# SCH_TempBoard-vB_2024-06-08.net
KiCad netlist of a schematic drawn in EasyEDA
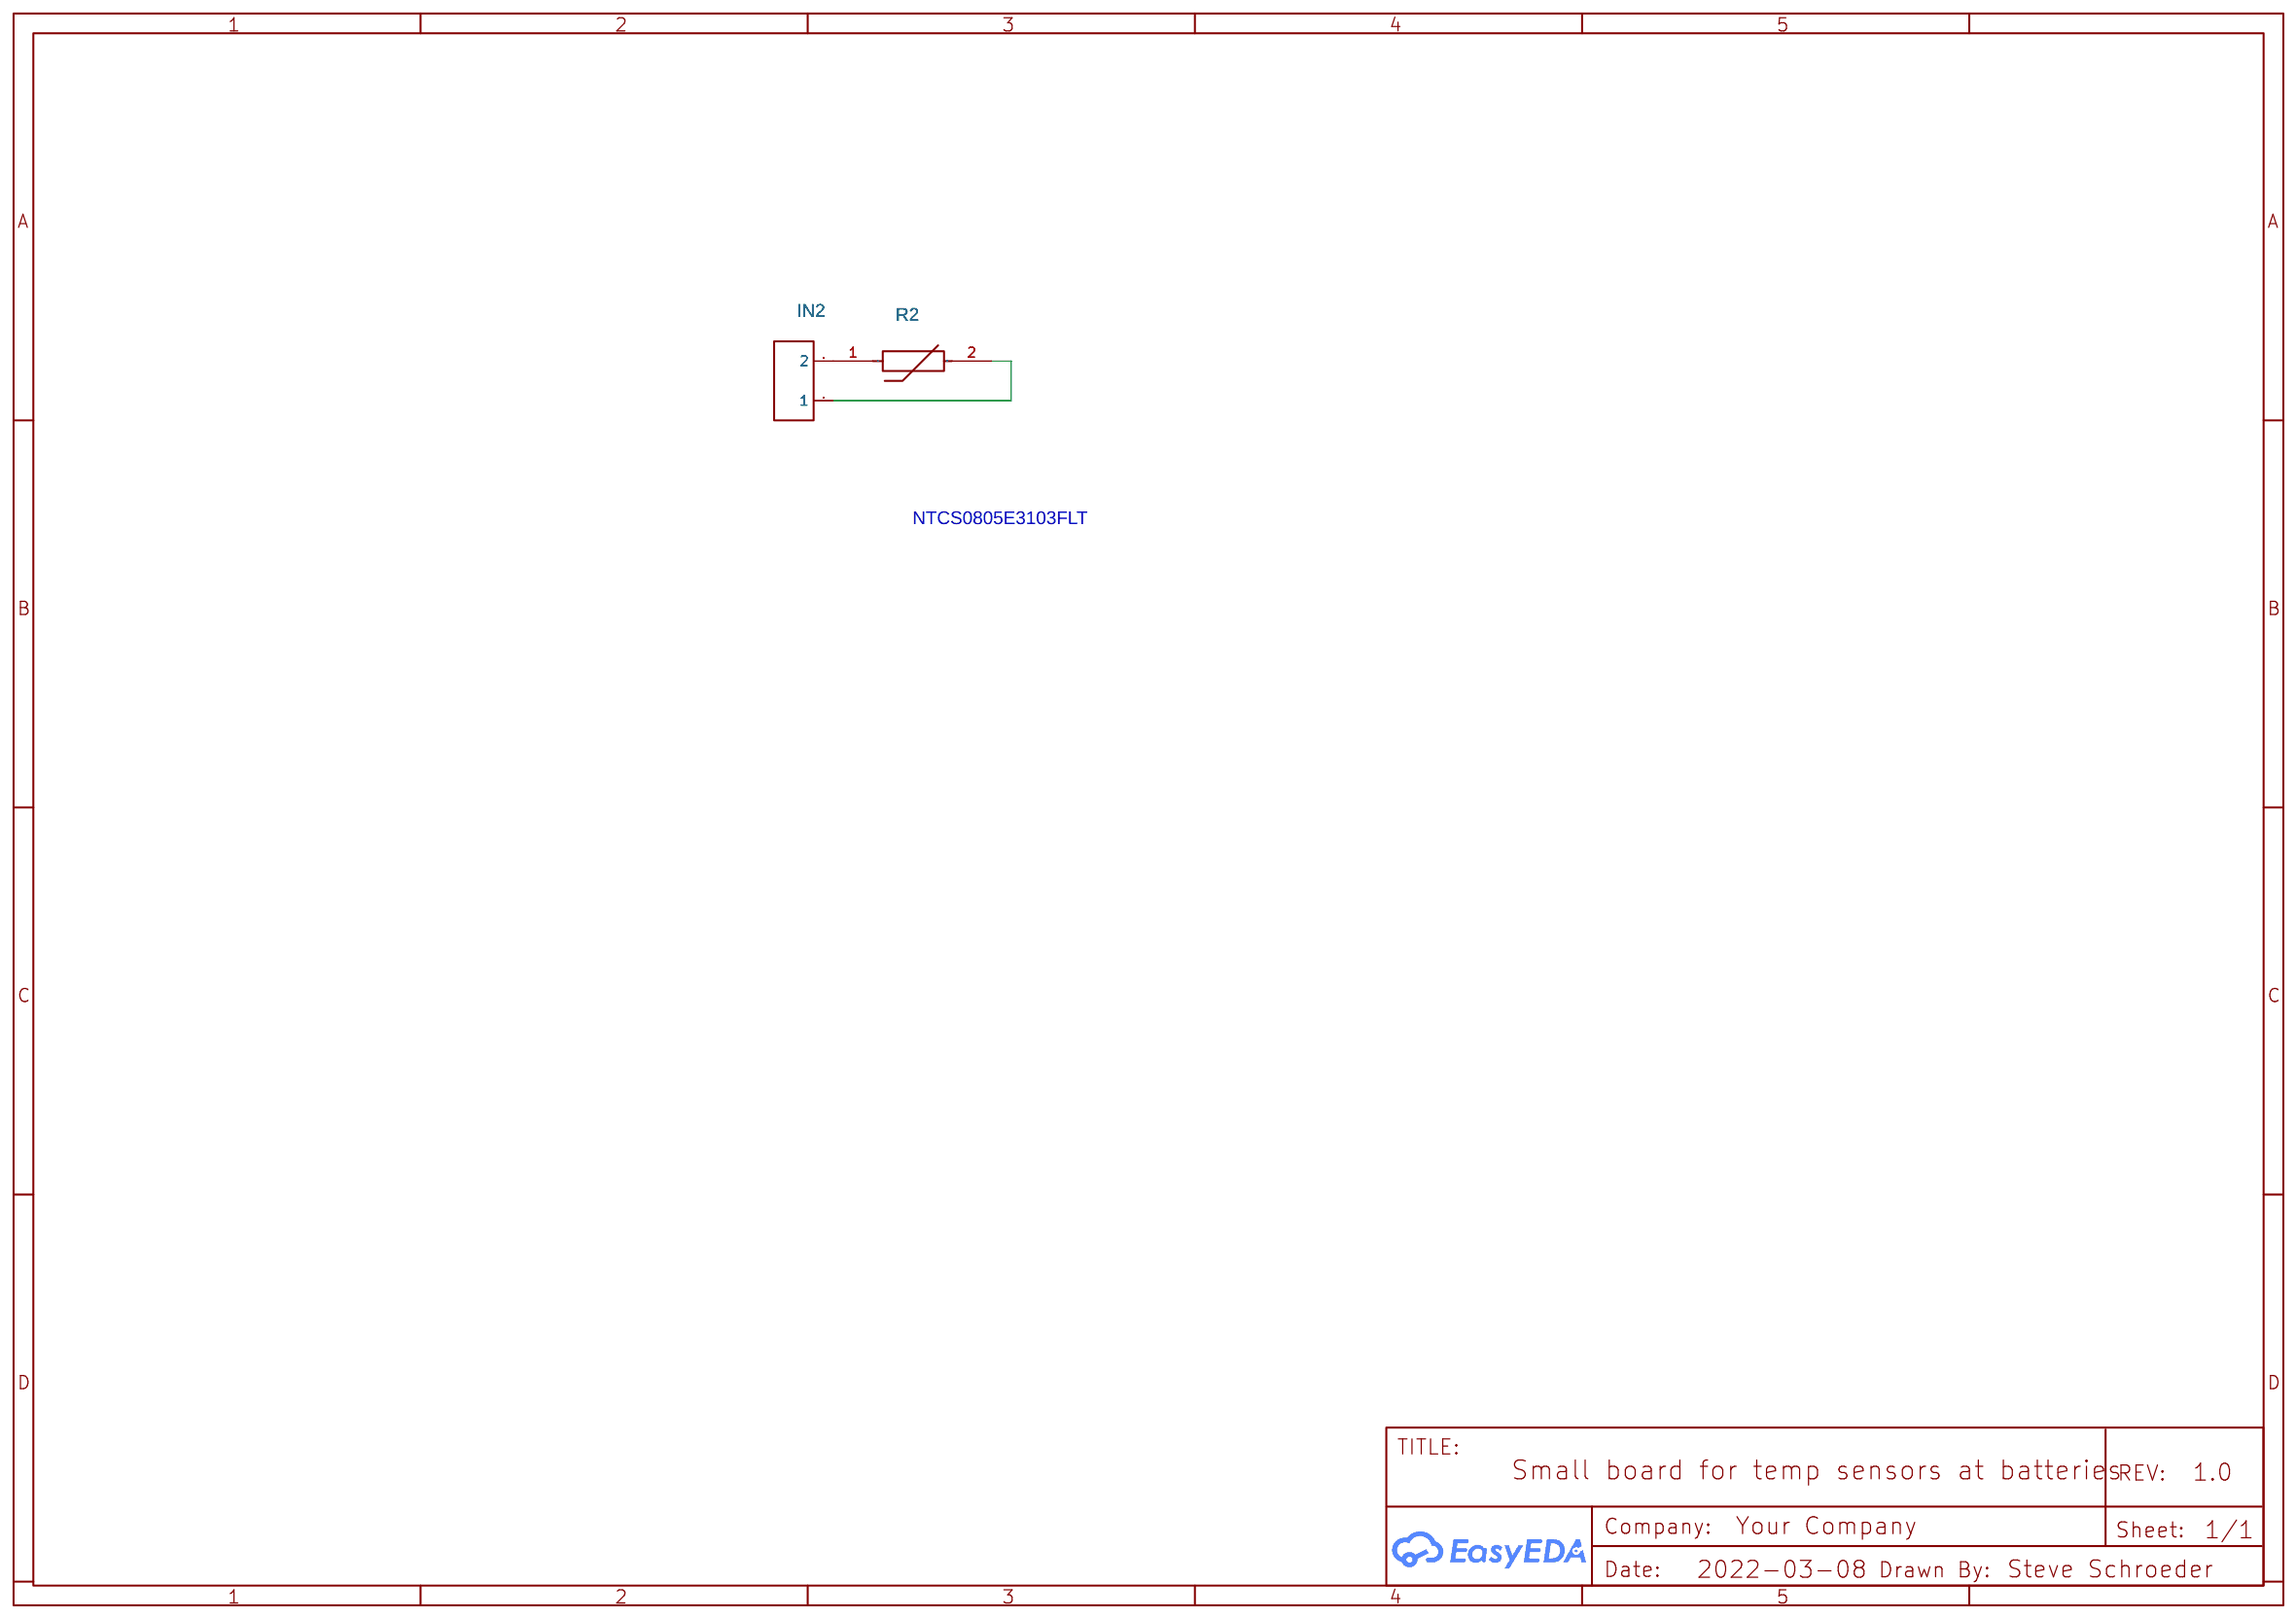
[diagram p0: schematic sheet]

(export (version "E")
  (design (tool "Eeschema 10.0.6"))
  (components
    (comp (ref "IN2")
      (value "Header-Male-2.54_1x2")
      (fields (field (name "Manufacturer Part") "826629-2") (field (name "Manufacturer") "TE Connectivity"))
      (libsource (lib "") (part "Header-Male-2.54_1x2"))
    )
    (comp (ref "R2")
      (value "NTCS0805E3103JHT")
      (fields (field (name "Manufacturer") "Vishay Intertech"))
      (libsource (lib "") (part "NTCS0805E3103JHT"))
    )
  )
  (nets
    (net (code "1") (name "Net-(IN2-Pad1)") (class "Default")
      (node (ref "IN2") (pin "1") (pinfunction "1_1") (pintype "unspecified"))
      (node (ref "R2") (pin "2") (pinfunction "2_2") (pintype "unspecified"))
    )
    (net (code "2") (name "Net-(IN2-Pad2)") (class "Default")
      (node (ref "IN2") (pin "2") (pinfunction "2_2") (pintype "unspecified"))
      (node (ref "R2") (pin "1") (pinfunction "1_1") (pintype "unspecified"))
    )
  )
)
